# ATZB-RF-233-1-C-RPI-Breakout.net
KiCad netlist of a schematic drawn in EAGLE
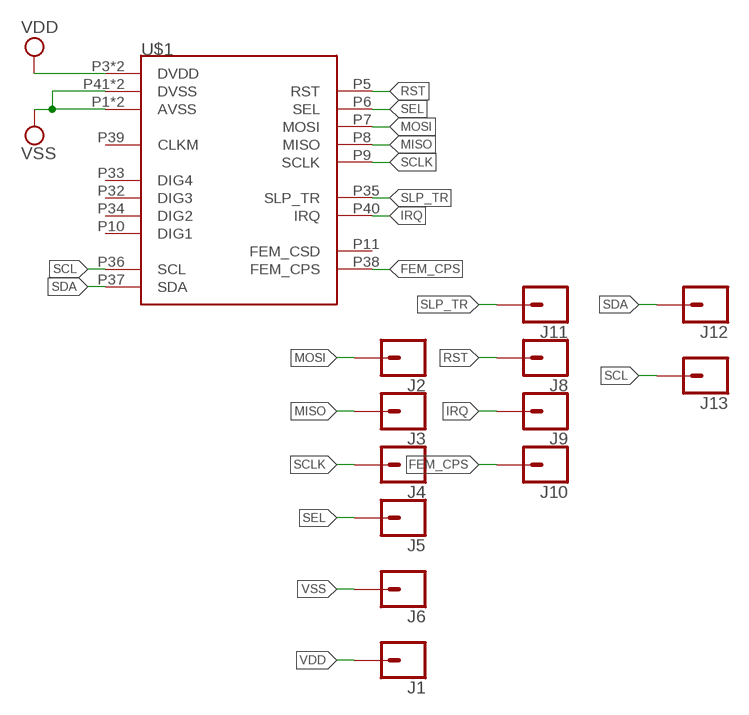
[diagram p0: schematic, sheet 1]

(export (version "E")
  (design (tool "Eeschema 10.0.6"))
  (components
    (comp (ref "J1")
      (value "CONN_01OFFSET")
      (footprint "eagle-import:1X01_OFFSET")
      (libsource (lib "eagle-import") (part "CONN_01OFFSET"))
    )
    (comp (ref "J2")
      (value "CONN_01OFFSET")
      (footprint "eagle-import:1X01_OFFSET")
      (libsource (lib "eagle-import") (part "CONN_01OFFSET"))
    )
    (comp (ref "J3")
      (value "CONN_01OFFSET")
      (footprint "eagle-import:1X01_OFFSET")
      (libsource (lib "eagle-import") (part "CONN_01OFFSET"))
    )
    (comp (ref "J4")
      (value "CONN_01OFFSET")
      (footprint "eagle-import:1X01_OFFSET")
      (libsource (lib "eagle-import") (part "CONN_01OFFSET"))
    )
    (comp (ref "J5")
      (value "CONN_01OFFSET")
      (footprint "eagle-import:1X01_OFFSET")
      (libsource (lib "eagle-import") (part "CONN_01OFFSET"))
    )
    (comp (ref "J6")
      (value "CONN_01OFFSET")
      (footprint "eagle-import:1X01_OFFSET")
      (libsource (lib "eagle-import") (part "CONN_01OFFSET"))
    )
    (comp (ref "J8")
      (value "CONN_01OFFSET")
      (footprint "eagle-import:1X01_OFFSET")
      (libsource (lib "eagle-import") (part "CONN_01OFFSET"))
    )
    (comp (ref "J9")
      (value "CONN_01OFFSET")
      (footprint "eagle-import:1X01_OFFSET")
      (libsource (lib "eagle-import") (part "CONN_01OFFSET"))
    )
    (comp (ref "J10")
      (value "CONN_01OFFSET")
      (footprint "eagle-import:1X01_OFFSET")
      (libsource (lib "eagle-import") (part "CONN_01OFFSET"))
    )
    (comp (ref "J11")
      (value "CONN_01OFFSET")
      (footprint "eagle-import:1X01_OFFSET")
      (libsource (lib "eagle-import") (part "CONN_01OFFSET"))
    )
    (comp (ref "J12")
      (value "CONN_01OFFSET")
      (footprint "eagle-import:1X01_OFFSET")
      (libsource (lib "eagle-import") (part "CONN_01OFFSET"))
    )
    (comp (ref "J13")
      (value "CONN_01OFFSET")
      (footprint "eagle-import:1X01_OFFSET")
      (libsource (lib "eagle-import") (part "CONN_01OFFSET"))
    )
    (comp (ref "U$1")
      (value "ATZB-RF-233-1-C")
      (footprint "eagle-import:ATZB-RF-233-1-C")
      (libsource (lib "eagle-import") (part "ATZB-RF-233-1-C"))
    )
  )
  (nets
    (net (code "1") (name "FEM_CPS") (class "Default")
      (node (ref "J10") (pin "1") (pinfunction "1_1") (pintype "passive"))
      (node (ref "U$1") (pin "P38") (pinfunction "FEM_CPS_P38") (pintype "bidirectional"))
    )
    (net (code "2") (name "IRQ") (class "Default")
      (node (ref "J9") (pin "1") (pinfunction "1_1") (pintype "passive"))
      (node (ref "U$1") (pin "P40") (pinfunction "IRQ_P40") (pintype "bidirectional"))
    )
    (net (code "3") (name "MISO") (class "Default")
      (node (ref "J3") (pin "1") (pinfunction "1_1") (pintype "passive"))
      (node (ref "U$1") (pin "P8") (pinfunction "MISO_P8") (pintype "bidirectional"))
    )
    (net (code "4") (name "MOSI") (class "Default")
      (node (ref "J2") (pin "1") (pinfunction "1_1") (pintype "passive"))
      (node (ref "U$1") (pin "P7") (pinfunction "MOSI_P7") (pintype "bidirectional"))
    )
    (net (code "5") (name "RST") (class "Default")
      (node (ref "J8") (pin "1") (pinfunction "1_1") (pintype "passive"))
      (node (ref "U$1") (pin "P5") (pinfunction "RST_P5") (pintype "bidirectional"))
    )
    (net (code "6") (name "SCL") (class "Default")
      (node (ref "J13") (pin "1") (pinfunction "1_1") (pintype "passive"))
      (node (ref "U$1") (pin "P36") (pinfunction "SCL_P36") (pintype "bidirectional"))
    )
    (net (code "7") (name "SCLK") (class "Default")
      (node (ref "J4") (pin "1") (pinfunction "1_1") (pintype "passive"))
      (node (ref "U$1") (pin "P9") (pinfunction "SCLK_P9") (pintype "bidirectional"))
    )
    (net (code "8") (name "SDA") (class "Default")
      (node (ref "J12") (pin "1") (pinfunction "1_1") (pintype "passive"))
      (node (ref "U$1") (pin "P37") (pinfunction "SDA_P37") (pintype "bidirectional"))
    )
    (net (code "9") (name "SEL") (class "Default")
      (node (ref "J5") (pin "1") (pinfunction "1_1") (pintype "passive"))
      (node (ref "U$1") (pin "P6") (pinfunction "SEL_P6") (pintype "bidirectional"))
    )
    (net (code "10") (name "SLP_TR") (class "Default")
      (node (ref "J11") (pin "1") (pinfunction "1_1") (pintype "passive"))
      (node (ref "U$1") (pin "P35") (pinfunction "SLP_TR_P35") (pintype "bidirectional"))
    )
    (net (code "11") (name "VDD") (class "Default")
      (node (ref "J1") (pin "1") (pinfunction "1_1") (pintype "passive"))
      (node (ref "U$1") (pin "P3") (pinfunction "DVDD_P3") (pintype "bidirectional"))
      (node (ref "U$1") (pin "P4") (pinfunction "DVDD_P4") (pintype "bidirectional"))
    )
    (net (code "12") (name "VSS") (class "Default")
      (node (ref "J6") (pin "1") (pinfunction "1_1") (pintype "passive"))
      (node (ref "U$1") (pin "P1") (pinfunction "AVSS_P1") (pintype "bidirectional"))
      (node (ref "U$1") (pin "P2") (pinfunction "AVSS_P2") (pintype "bidirectional"))
      (node (ref "U$1") (pin "P41") (pinfunction "DVSS_P41") (pintype "bidirectional"))
      (node (ref "U$1") (pin "P42") (pinfunction "DVSS_P42") (pintype "bidirectional"))
    )
    (net (code "13") (name "unconnected-(U$1-CLKM-PadP39)") (class "Default")
      (node (ref "U$1") (pin "P39") (pinfunction "CLKM_P39") (pintype "bidirectional"))
    )
    (net (code "14") (name "unconnected-(U$1-DIG1-PadP10)") (class "Default")
      (node (ref "U$1") (pin "P10") (pinfunction "DIG1_P10") (pintype "bidirectional"))
    )
    (net (code "15") (name "unconnected-(U$1-DIG2-PadP34)") (class "Default")
      (node (ref "U$1") (pin "P34") (pinfunction "DIG2_P34") (pintype "bidirectional"))
    )
    (net (code "16") (name "unconnected-(U$1-DIG3-PadP32)") (class "Default")
      (node (ref "U$1") (pin "P32") (pinfunction "DIG3_P32") (pintype "bidirectional"))
    )
    (net (code "17") (name "unconnected-(U$1-DIG4-PadP33)") (class "Default")
      (node (ref "U$1") (pin "P33") (pinfunction "DIG4_P33") (pintype "bidirectional"))
    )
    (net (code "18") (name "unconnected-(U$1-FEM_CSD-PadP11)") (class "Default")
      (node (ref "U$1") (pin "P11") (pinfunction "FEM_CSD_P11") (pintype "bidirectional"))
    )
  )
)
